# adaptateur_fusible.net
KiCad netlist of a schematic drawn in EAGLE
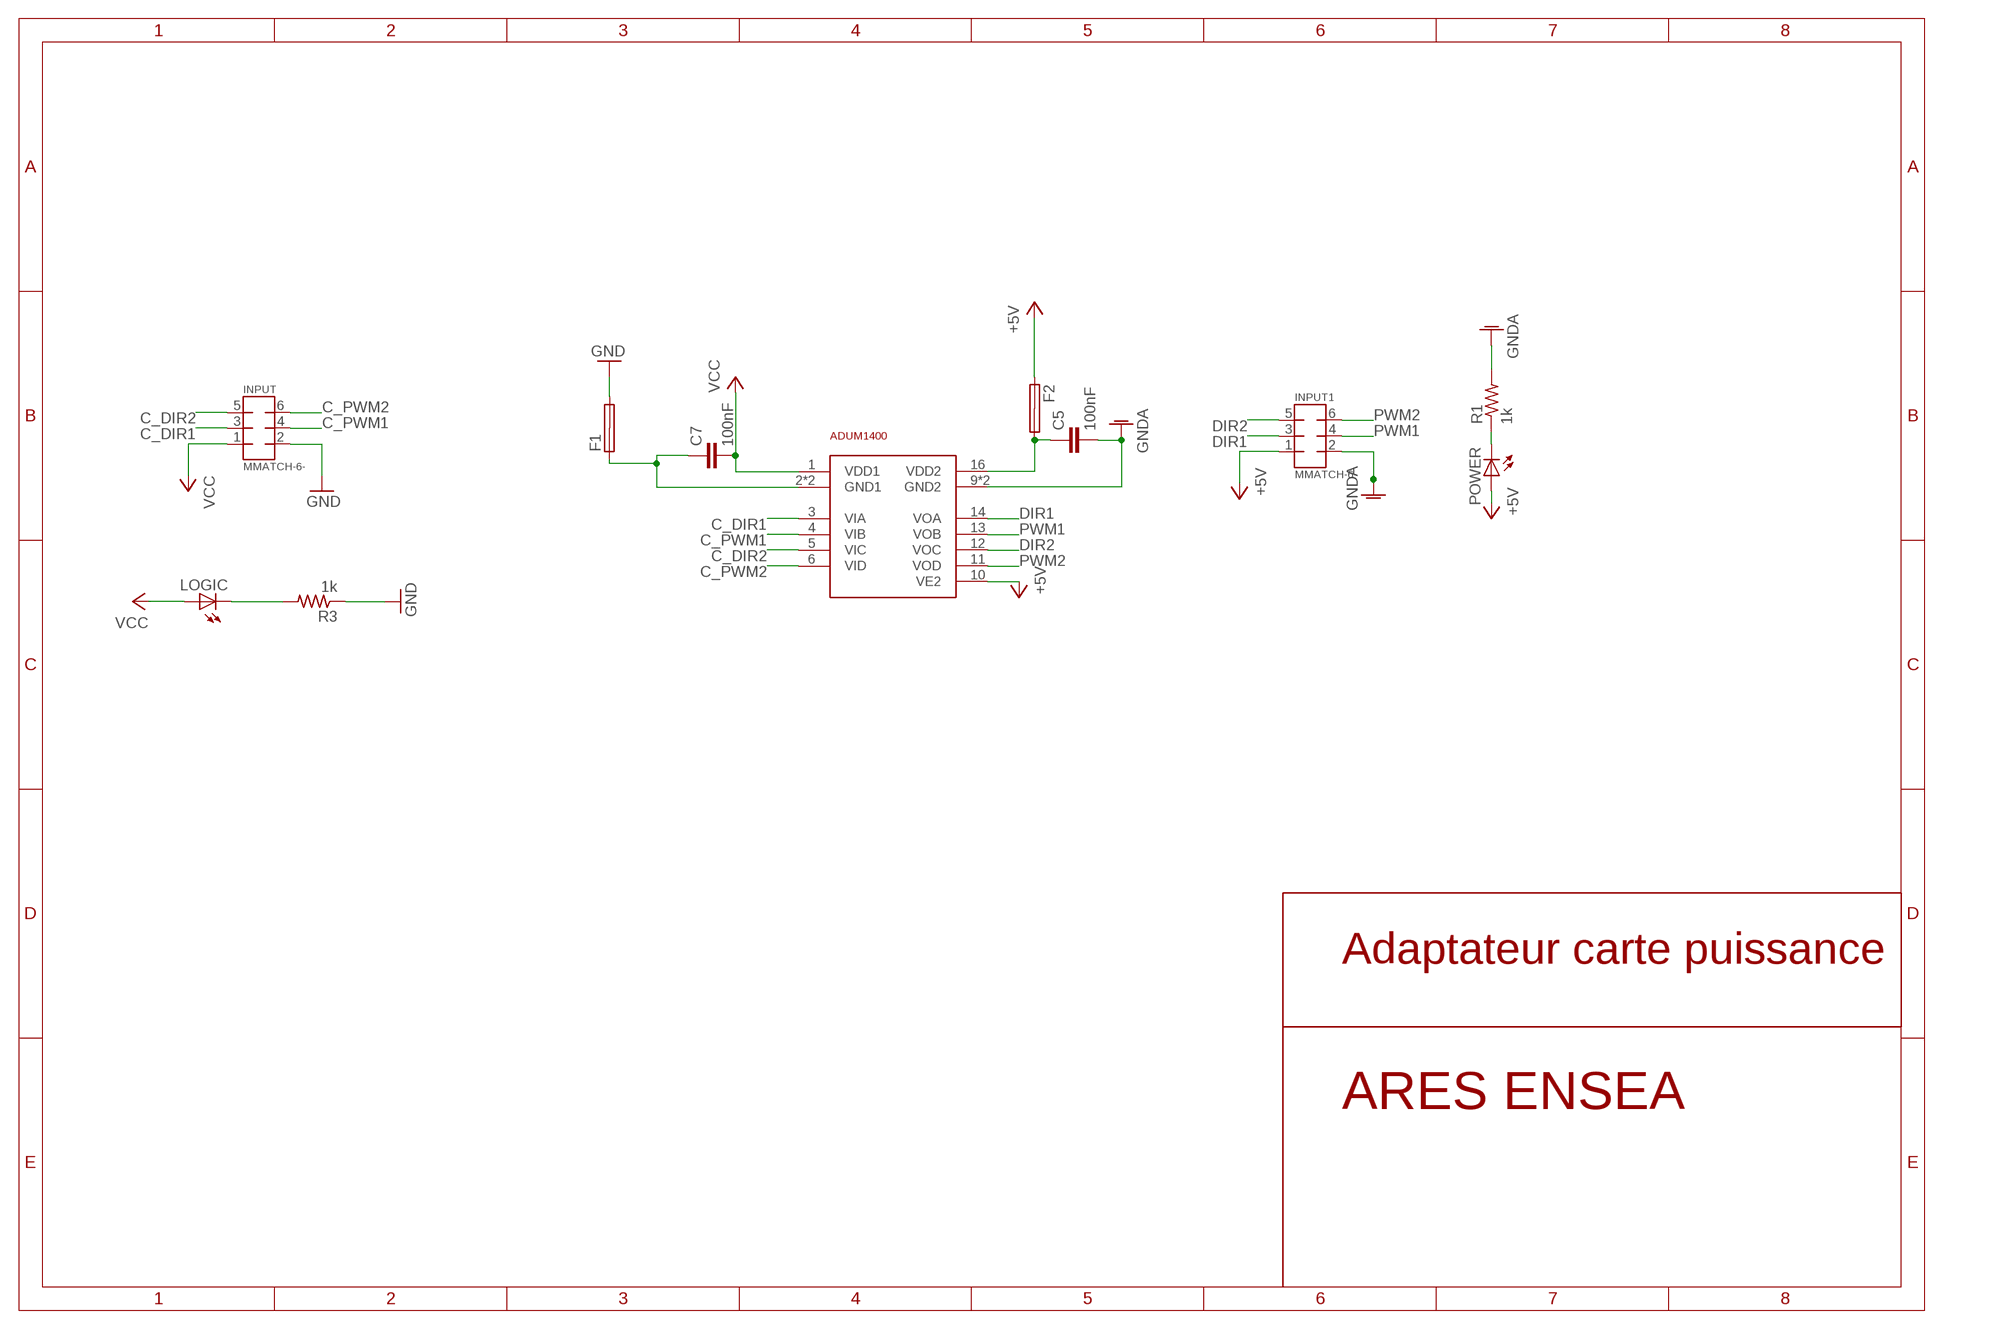
[diagram p0: schematic, sheet 1]

(export (version "E")
  (design (tool "Eeschema 10.0.6"))
  (components
    (comp (ref "C5")
      (value "100nF")
      (footprint "eagle-import:C0805")
      (libsource (lib "eagle-import") (part "C-EUC0805"))
    )
    (comp (ref "C7")
      (value "100nF")
      (footprint "eagle-import:C0805")
      (libsource (lib "eagle-import") (part "C-EUC0805"))
    )
    (comp (ref "F1")
      (value "SHK20Q")
      (footprint "eagle-import:SHK20Q")
      (libsource (lib "eagle-import") (part "SHK20Q"))
    )
    (comp (ref "F2")
      (value "SHK20Q")
      (footprint "eagle-import:SHK20Q")
      (libsource (lib "eagle-import") (part "SHK20Q"))
    )
    (comp (ref "INPUT")
      (value "MMATCH-6-")
      (footprint "eagle-import:AMP-215079-6")
      (libsource (lib "eagle-import") (part "MMATCH-6-"))
    )
    (comp (ref "INPUT1")
      (value "MMATCH-6-")
      (footprint "eagle-import:AMP-215079-6")
      (libsource (lib "eagle-import") (part "MMATCH-6-"))
    )
    (comp (ref "LOGIC")
      (value "LEDSML0805")
      (footprint "eagle-import:SML0805")
      (libsource (lib "eagle-import") (part "LEDSML0805"))
    )
    (comp (ref "POWER")
      (value "LEDSML0805")
      (footprint "eagle-import:SML0805")
      (libsource (lib "eagle-import") (part "LEDSML0805"))
    )
    (comp (ref "R1")
      (value "1k")
      (footprint "eagle-import:M0805")
      (libsource (lib "eagle-import") (part "R-US_M0805"))
    )
    (comp (ref "R3")
      (value "1k")
      (footprint "eagle-import:M0805")
      (libsource (lib "eagle-import") (part "R-US_M0805"))
    )
    (comp (ref "U$3")
      (value "ADUM1400S")
      (footprint "eagle-import:SO-16W")
      (libsource (lib "eagle-import") (part "ADUM1400S"))
    )
  )
  (nets
    (net (code "1") (name "+5V") (class "Default")
      (node (ref "F2") (pin "1A") (pinfunction "1A_1A") (pintype "passive"))
      (node (ref "INPUT1") (pin "1") (pinfunction "3_1") (pintype "bidirectional"))
      (node (ref "POWER") (pin "A") (pinfunction "A_A") (pintype "passive"))
      (node (ref "U$3") (pin "10") (pinfunction "VE2_10") (pintype "bidirectional"))
    )
    (net (code "2") (name "/C_DIR1") (class "Default")
      (node (ref "INPUT") (pin "3") (pinfunction "5_3") (pintype "bidirectional"))
      (node (ref "U$3") (pin "3") (pinfunction "VIA_3") (pintype "bidirectional"))
    )
    (net (code "3") (name "/C_DIR2") (class "Default")
      (node (ref "INPUT") (pin "5") (pinfunction "7_5") (pintype "bidirectional"))
      (node (ref "U$3") (pin "5") (pinfunction "VIC_5") (pintype "bidirectional"))
    )
    (net (code "4") (name "/C_PWM1") (class "Default")
      (node (ref "INPUT") (pin "4") (pinfunction "6_4") (pintype "bidirectional"))
      (node (ref "U$3") (pin "4") (pinfunction "VIB_4") (pintype "bidirectional"))
    )
    (net (code "5") (name "/C_PWM2") (class "Default")
      (node (ref "INPUT") (pin "6") (pinfunction "8_6") (pintype "bidirectional"))
      (node (ref "U$3") (pin "6") (pinfunction "VID_6") (pintype "bidirectional"))
    )
    (net (code "6") (name "/DIR1") (class "Default")
      (node (ref "INPUT1") (pin "3") (pinfunction "5_3") (pintype "bidirectional"))
      (node (ref "U$3") (pin "14") (pinfunction "VOA_14") (pintype "bidirectional"))
    )
    (net (code "7") (name "/DIR2") (class "Default")
      (node (ref "INPUT1") (pin "5") (pinfunction "7_5") (pintype "bidirectional"))
      (node (ref "U$3") (pin "12") (pinfunction "VOC_12") (pintype "bidirectional"))
    )
    (net (code "8") (name "/PWM1") (class "Default")
      (node (ref "INPUT1") (pin "4") (pinfunction "6_4") (pintype "bidirectional"))
      (node (ref "U$3") (pin "13") (pinfunction "VOB_13") (pintype "bidirectional"))
    )
    (net (code "9") (name "/PWM2") (class "Default")
      (node (ref "INPUT1") (pin "6") (pinfunction "8_6") (pintype "bidirectional"))
      (node (ref "U$3") (pin "11") (pinfunction "VOD_11") (pintype "bidirectional"))
    )
    (net (code "10") (name "GND") (class "Default")
      (node (ref "F1") (pin "2A") (pinfunction "2A_2A") (pintype "passive"))
      (node (ref "INPUT") (pin "2") (pinfunction "4_2") (pintype "bidirectional"))
      (node (ref "R3") (pin "1") (pinfunction "1_1") (pintype "passive"))
    )
    (net (code "11") (name "GNDA") (class "Default")
      (node (ref "C5") (pin "2") (pinfunction "2_2") (pintype "passive"))
      (node (ref "INPUT1") (pin "2") (pinfunction "4_2") (pintype "bidirectional"))
      (node (ref "R1") (pin "2") (pinfunction "2_2") (pintype "passive"))
      (node (ref "U$3") (pin "15") (pinfunction "GND2_15") (pintype "bidirectional"))
      (node (ref "U$3") (pin "9") (pinfunction "GND2_9") (pintype "bidirectional"))
    )
    (net (code "12") (name "Net-(C7-Pad1)") (class "Default")
      (node (ref "C7") (pin "1") (pinfunction "1_1") (pintype "passive"))
      (node (ref "F1") (pin "1A") (pinfunction "1A_1A") (pintype "passive"))
      (node (ref "U$3") (pin "2") (pinfunction "GND1_2") (pintype "bidirectional"))
      (node (ref "U$3") (pin "8") (pinfunction "GND1_8") (pintype "bidirectional"))
    )
    (net (code "13") (name "Net-(LOGIC-PadC)") (class "Default")
      (node (ref "LOGIC") (pin "C") (pinfunction "C_C") (pintype "passive"))
      (node (ref "R3") (pin "2") (pinfunction "2_2") (pintype "passive"))
    )
    (net (code "14") (name "Net-(POWER-PadC)") (class "Default")
      (node (ref "POWER") (pin "C") (pinfunction "C_C") (pintype "passive"))
      (node (ref "R1") (pin "1") (pinfunction "1_1") (pintype "passive"))
    )
    (net (code "15") (name "Net-(U$3-VDD2)") (class "Default")
      (node (ref "C5") (pin "1") (pinfunction "1_1") (pintype "passive"))
      (node (ref "F2") (pin "2A") (pinfunction "2A_2A") (pintype "passive"))
      (node (ref "U$3") (pin "16") (pinfunction "VDD2_16") (pintype "bidirectional"))
    )
    (net (code "16") (name "VCC") (class "Default")
      (node (ref "C7") (pin "2") (pinfunction "2_2") (pintype "passive"))
      (node (ref "INPUT") (pin "1") (pinfunction "3_1") (pintype "bidirectional"))
      (node (ref "LOGIC") (pin "A") (pinfunction "A_A") (pintype "passive"))
      (node (ref "U$3") (pin "1") (pinfunction "VDD1_1") (pintype "bidirectional"))
    )
    (net (code "17") (name "unconnected-(F1-Pad1B)") (class "Default")
      (node (ref "F1") (pin "1B") (pinfunction "1B_1B") (pintype "passive"))
    )
    (net (code "18") (name "unconnected-(F1-Pad2B)") (class "Default")
      (node (ref "F1") (pin "2B") (pinfunction "2B_2B") (pintype "passive"))
    )
    (net (code "19") (name "unconnected-(F2-Pad1B)") (class "Default")
      (node (ref "F2") (pin "1B") (pinfunction "1B_1B") (pintype "passive"))
    )
    (net (code "20") (name "unconnected-(F2-Pad2B)") (class "Default")
      (node (ref "F2") (pin "2B") (pinfunction "2B_2B") (pintype "passive"))
    )
  )
)
